# 16-key_Pro_Micro.net
KiCad netlist of a schematic drawn in EAGLE
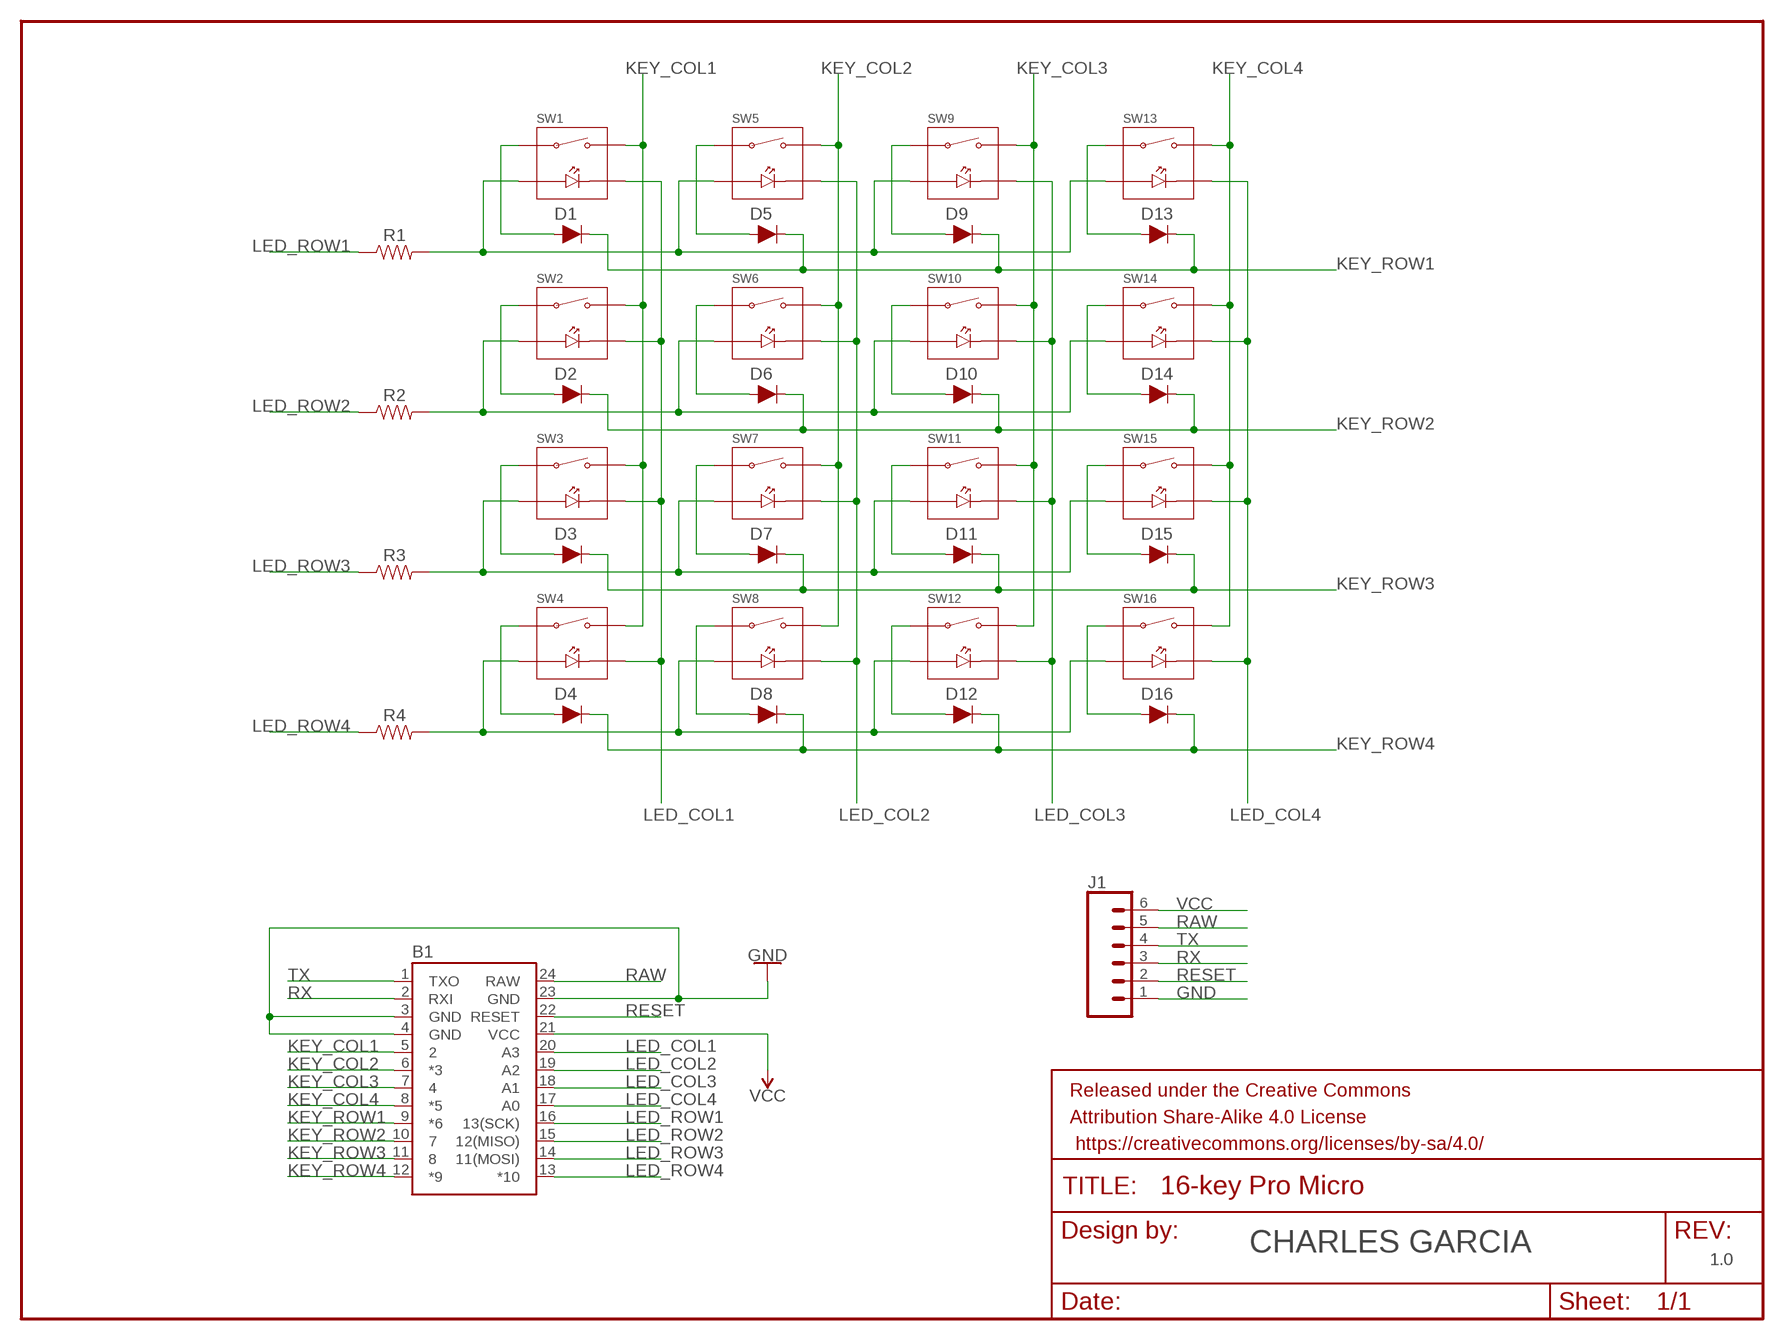
[diagram p0: schematic, sheet 1]

(export (version "E")
  (design (tool "Eeschema 10.0.6"))
  (components
    (comp (ref "B1")
      (value "SPARKFUN_PRO_MICRO")
      (footprint "eagle-import:SPARKFUN_PRO_MICRO")
      (libsource (lib "eagle-import") (part "SPARKFUN_PRO_MICRO"))
    )
    (comp (ref "D1")
      (value "DIODE-1N4148")
      (footprint "eagle-import:DIODE-1N4148")
      (libsource (lib "eagle-import") (part "DIODE-1N4148"))
    )
    (comp (ref "D2")
      (value "DIODE-1N4148")
      (footprint "eagle-import:DIODE-1N4148")
      (libsource (lib "eagle-import") (part "DIODE-1N4148"))
    )
    (comp (ref "D3")
      (value "DIODE-1N4148")
      (footprint "eagle-import:DIODE-1N4148")
      (libsource (lib "eagle-import") (part "DIODE-1N4148"))
    )
    (comp (ref "D4")
      (value "DIODE-1N4148")
      (footprint "eagle-import:DIODE-1N4148")
      (libsource (lib "eagle-import") (part "DIODE-1N4148"))
    )
    (comp (ref "D5")
      (value "DIODE-1N4148")
      (footprint "eagle-import:DIODE-1N4148")
      (libsource (lib "eagle-import") (part "DIODE-1N4148"))
    )
    (comp (ref "D6")
      (value "DIODE-1N4148")
      (footprint "eagle-import:DIODE-1N4148")
      (libsource (lib "eagle-import") (part "DIODE-1N4148"))
    )
    (comp (ref "D7")
      (value "DIODE-1N4148")
      (footprint "eagle-import:DIODE-1N4148")
      (libsource (lib "eagle-import") (part "DIODE-1N4148"))
    )
    (comp (ref "D8")
      (value "DIODE-1N4148")
      (footprint "eagle-import:DIODE-1N4148")
      (libsource (lib "eagle-import") (part "DIODE-1N4148"))
    )
    (comp (ref "D9")
      (value "DIODE-1N4148")
      (footprint "eagle-import:DIODE-1N4148")
      (libsource (lib "eagle-import") (part "DIODE-1N4148"))
    )
    (comp (ref "D10")
      (value "DIODE-1N4148")
      (footprint "eagle-import:DIODE-1N4148")
      (libsource (lib "eagle-import") (part "DIODE-1N4148"))
    )
    (comp (ref "D11")
      (value "DIODE-1N4148")
      (footprint "eagle-import:DIODE-1N4148")
      (libsource (lib "eagle-import") (part "DIODE-1N4148"))
    )
    (comp (ref "D12")
      (value "DIODE-1N4148")
      (footprint "eagle-import:DIODE-1N4148")
      (libsource (lib "eagle-import") (part "DIODE-1N4148"))
    )
    (comp (ref "D13")
      (value "DIODE-1N4148")
      (footprint "eagle-import:DIODE-1N4148")
      (libsource (lib "eagle-import") (part "DIODE-1N4148"))
    )
    (comp (ref "D14")
      (value "DIODE-1N4148")
      (footprint "eagle-import:DIODE-1N4148")
      (libsource (lib "eagle-import") (part "DIODE-1N4148"))
    )
    (comp (ref "D15")
      (value "DIODE-1N4148")
      (footprint "eagle-import:DIODE-1N4148")
      (libsource (lib "eagle-import") (part "DIODE-1N4148"))
    )
    (comp (ref "D16")
      (value "DIODE-1N4148")
      (footprint "eagle-import:DIODE-1N4148")
      (libsource (lib "eagle-import") (part "DIODE-1N4148"))
    )
    (comp (ref "FRAME1")
      (value "FRAME-LETTER")
      (footprint "eagle-import:CREATIVE_COMMONS")
      (fields (field (name "AUTHOR") "CHARLES GARCIA") (field (name "REV") "1.0"))
      (libsource (lib "eagle-import") (part "FRAME-LETTER"))
    )
    (comp (ref "J1")
      (value "CONN_06SILK_FEMALE_PTH")
      (footprint "eagle-import:1X06")
      (libsource (lib "eagle-import") (part "CONN_06SILK_FEMALE_PTH"))
    )
    (comp (ref "R1")
      (value "RESISTORAXIAL-0.3")
      (footprint "eagle-import:AXIAL-0.3")
      (libsource (lib "eagle-import") (part "RESISTORAXIAL-0.3"))
    )
    (comp (ref "R2")
      (value "RESISTORAXIAL-0.3")
      (footprint "eagle-import:AXIAL-0.3")
      (libsource (lib "eagle-import") (part "RESISTORAXIAL-0.3"))
    )
    (comp (ref "R3")
      (value "RESISTORAXIAL-0.3")
      (footprint "eagle-import:AXIAL-0.3")
      (libsource (lib "eagle-import") (part "RESISTORAXIAL-0.3"))
    )
    (comp (ref "R4")
      (value "RESISTORAXIAL-0.3")
      (footprint "eagle-import:AXIAL-0.3")
      (libsource (lib "eagle-import") (part "RESISTORAXIAL-0.3"))
    )
    (comp (ref "SW1")
      (value "CHERRY_MX_PCB_LED")
      (footprint "eagle-import:MX_PCB_MOUNT_LED")
      (libsource (lib "eagle-import") (part "CHERRY_MX_PCB_LED"))
    )
    (comp (ref "SW2")
      (value "CHERRY_MX_PCB_LED")
      (footprint "eagle-import:MX_PCB_MOUNT_LED")
      (libsource (lib "eagle-import") (part "CHERRY_MX_PCB_LED"))
    )
    (comp (ref "SW3")
      (value "CHERRY_MX_PCB_LED")
      (footprint "eagle-import:MX_PCB_MOUNT_LED")
      (libsource (lib "eagle-import") (part "CHERRY_MX_PCB_LED"))
    )
    (comp (ref "SW4")
      (value "CHERRY_MX_PCB_LED")
      (footprint "eagle-import:MX_PCB_MOUNT_LED")
      (libsource (lib "eagle-import") (part "CHERRY_MX_PCB_LED"))
    )
    (comp (ref "SW5")
      (value "CHERRY_MX_PCB_LED")
      (footprint "eagle-import:MX_PCB_MOUNT_LED")
      (libsource (lib "eagle-import") (part "CHERRY_MX_PCB_LED"))
    )
    (comp (ref "SW6")
      (value "CHERRY_MX_PCB_LED")
      (footprint "eagle-import:MX_PCB_MOUNT_LED")
      (libsource (lib "eagle-import") (part "CHERRY_MX_PCB_LED"))
    )
    (comp (ref "SW7")
      (value "CHERRY_MX_PCB_LED")
      (footprint "eagle-import:MX_PCB_MOUNT_LED")
      (libsource (lib "eagle-import") (part "CHERRY_MX_PCB_LED"))
    )
    (comp (ref "SW8")
      (value "CHERRY_MX_PCB_LED")
      (footprint "eagle-import:MX_PCB_MOUNT_LED")
      (libsource (lib "eagle-import") (part "CHERRY_MX_PCB_LED"))
    )
    (comp (ref "SW9")
      (value "CHERRY_MX_PCB_LED")
      (footprint "eagle-import:MX_PCB_MOUNT_LED")
      (libsource (lib "eagle-import") (part "CHERRY_MX_PCB_LED"))
    )
    (comp (ref "SW10")
      (value "CHERRY_MX_PCB_LED")
      (footprint "eagle-import:MX_PCB_MOUNT_LED")
      (libsource (lib "eagle-import") (part "CHERRY_MX_PCB_LED"))
    )
    (comp (ref "SW11")
      (value "CHERRY_MX_PCB_LED")
      (footprint "eagle-import:MX_PCB_MOUNT_LED")
      (libsource (lib "eagle-import") (part "CHERRY_MX_PCB_LED"))
    )
    (comp (ref "SW12")
      (value "CHERRY_MX_PCB_LED")
      (footprint "eagle-import:MX_PCB_MOUNT_LED")
      (libsource (lib "eagle-import") (part "CHERRY_MX_PCB_LED"))
    )
    (comp (ref "SW13")
      (value "CHERRY_MX_PCB_LED")
      (footprint "eagle-import:MX_PCB_MOUNT_LED")
      (libsource (lib "eagle-import") (part "CHERRY_MX_PCB_LED"))
    )
    (comp (ref "SW14")
      (value "CHERRY_MX_PCB_LED")
      (footprint "eagle-import:MX_PCB_MOUNT_LED")
      (libsource (lib "eagle-import") (part "CHERRY_MX_PCB_LED"))
    )
    (comp (ref "SW15")
      (value "CHERRY_MX_PCB_LED")
      (footprint "eagle-import:MX_PCB_MOUNT_LED")
      (libsource (lib "eagle-import") (part "CHERRY_MX_PCB_LED"))
    )
    (comp (ref "SW16")
      (value "CHERRY_MX_PCB_LED")
      (footprint "eagle-import:MX_PCB_MOUNT_LED")
      (libsource (lib "eagle-import") (part "CHERRY_MX_PCB_LED"))
    )
  )
  (nets
    (net (code "1") (name "/KEY_COL1") (class "Default")
      (node (ref "B1") (pin "5") (pinfunction "2_5") (pintype "bidirectional"))
      (node (ref "SW1") (pin "SW_OUT") (pinfunction "SW_OUT_SW_OUT") (pintype "bidirectional"))
      (node (ref "SW2") (pin "SW_OUT") (pinfunction "SW_OUT_SW_OUT") (pintype "bidirectional"))
      (node (ref "SW3") (pin "SW_OUT") (pinfunction "SW_OUT_SW_OUT") (pintype "bidirectional"))
      (node (ref "SW4") (pin "SW_OUT") (pinfunction "SW_OUT_SW_OUT") (pintype "bidirectional"))
    )
    (net (code "2") (name "/KEY_COL2") (class "Default")
      (node (ref "B1") (pin "6") (pinfunction "*3_6") (pintype "bidirectional"))
      (node (ref "SW5") (pin "SW_OUT") (pinfunction "SW_OUT_SW_OUT") (pintype "bidirectional"))
      (node (ref "SW6") (pin "SW_OUT") (pinfunction "SW_OUT_SW_OUT") (pintype "bidirectional"))
      (node (ref "SW7") (pin "SW_OUT") (pinfunction "SW_OUT_SW_OUT") (pintype "bidirectional"))
      (node (ref "SW8") (pin "SW_OUT") (pinfunction "SW_OUT_SW_OUT") (pintype "bidirectional"))
    )
    (net (code "3") (name "/KEY_COL3") (class "Default")
      (node (ref "B1") (pin "7") (pinfunction "4_7") (pintype "bidirectional"))
      (node (ref "SW10") (pin "SW_OUT") (pinfunction "SW_OUT_SW_OUT") (pintype "bidirectional"))
      (node (ref "SW11") (pin "SW_OUT") (pinfunction "SW_OUT_SW_OUT") (pintype "bidirectional"))
      (node (ref "SW12") (pin "SW_OUT") (pinfunction "SW_OUT_SW_OUT") (pintype "bidirectional"))
      (node (ref "SW9") (pin "SW_OUT") (pinfunction "SW_OUT_SW_OUT") (pintype "bidirectional"))
    )
    (net (code "4") (name "/KEY_COL4") (class "Default")
      (node (ref "B1") (pin "8") (pinfunction "*5_8") (pintype "bidirectional"))
      (node (ref "SW13") (pin "SW_OUT") (pinfunction "SW_OUT_SW_OUT") (pintype "bidirectional"))
      (node (ref "SW14") (pin "SW_OUT") (pinfunction "SW_OUT_SW_OUT") (pintype "bidirectional"))
      (node (ref "SW15") (pin "SW_OUT") (pinfunction "SW_OUT_SW_OUT") (pintype "bidirectional"))
      (node (ref "SW16") (pin "SW_OUT") (pinfunction "SW_OUT_SW_OUT") (pintype "bidirectional"))
    )
    (net (code "5") (name "/KEY_ROW1") (class "Default")
      (node (ref "B1") (pin "9") (pinfunction "*6_9") (pintype "bidirectional"))
      (node (ref "D1") (pin "C") (pinfunction "C_C") (pintype "passive"))
      (node (ref "D13") (pin "C") (pinfunction "C_C") (pintype "passive"))
      (node (ref "D5") (pin "C") (pinfunction "C_C") (pintype "passive"))
      (node (ref "D9") (pin "C") (pinfunction "C_C") (pintype "passive"))
    )
    (net (code "6") (name "/KEY_ROW2") (class "Default")
      (node (ref "B1") (pin "10") (pinfunction "7_10") (pintype "bidirectional"))
      (node (ref "D10") (pin "C") (pinfunction "C_C") (pintype "passive"))
      (node (ref "D14") (pin "C") (pinfunction "C_C") (pintype "passive"))
      (node (ref "D2") (pin "C") (pinfunction "C_C") (pintype "passive"))
      (node (ref "D6") (pin "C") (pinfunction "C_C") (pintype "passive"))
    )
    (net (code "7") (name "/KEY_ROW3") (class "Default")
      (node (ref "B1") (pin "11") (pinfunction "8_11") (pintype "bidirectional"))
      (node (ref "D11") (pin "C") (pinfunction "C_C") (pintype "passive"))
      (node (ref "D15") (pin "C") (pinfunction "C_C") (pintype "passive"))
      (node (ref "D3") (pin "C") (pinfunction "C_C") (pintype "passive"))
      (node (ref "D7") (pin "C") (pinfunction "C_C") (pintype "passive"))
    )
    (net (code "8") (name "/KEY_ROW4") (class "Default")
      (node (ref "B1") (pin "12") (pinfunction "*9_12") (pintype "bidirectional"))
      (node (ref "D12") (pin "C") (pinfunction "C_C") (pintype "passive"))
      (node (ref "D16") (pin "C") (pinfunction "C_C") (pintype "passive"))
      (node (ref "D4") (pin "C") (pinfunction "C_C") (pintype "passive"))
      (node (ref "D8") (pin "C") (pinfunction "C_C") (pintype "passive"))
    )
    (net (code "9") (name "/LED_COL1") (class "Default")
      (node (ref "B1") (pin "20") (pinfunction "A3_20") (pintype "bidirectional"))
      (node (ref "SW1") (pin "LED_OUT") (pinfunction "LED_OUT_LED_OUT") (pintype "bidirectional"))
      (node (ref "SW2") (pin "LED_OUT") (pinfunction "LED_OUT_LED_OUT") (pintype "bidirectional"))
      (node (ref "SW3") (pin "LED_OUT") (pinfunction "LED_OUT_LED_OUT") (pintype "bidirectional"))
      (node (ref "SW4") (pin "LED_OUT") (pinfunction "LED_OUT_LED_OUT") (pintype "bidirectional"))
    )
    (net (code "10") (name "/LED_COL2") (class "Default")
      (node (ref "B1") (pin "19") (pinfunction "A2_19") (pintype "bidirectional"))
      (node (ref "SW5") (pin "LED_OUT") (pinfunction "LED_OUT_LED_OUT") (pintype "bidirectional"))
      (node (ref "SW6") (pin "LED_OUT") (pinfunction "LED_OUT_LED_OUT") (pintype "bidirectional"))
      (node (ref "SW7") (pin "LED_OUT") (pinfunction "LED_OUT_LED_OUT") (pintype "bidirectional"))
      (node (ref "SW8") (pin "LED_OUT") (pinfunction "LED_OUT_LED_OUT") (pintype "bidirectional"))
    )
    (net (code "11") (name "/LED_COL3") (class "Default")
      (node (ref "B1") (pin "18") (pinfunction "A1_18") (pintype "bidirectional"))
      (node (ref "SW10") (pin "LED_OUT") (pinfunction "LED_OUT_LED_OUT") (pintype "bidirectional"))
      (node (ref "SW11") (pin "LED_OUT") (pinfunction "LED_OUT_LED_OUT") (pintype "bidirectional"))
      (node (ref "SW12") (pin "LED_OUT") (pinfunction "LED_OUT_LED_OUT") (pintype "bidirectional"))
      (node (ref "SW9") (pin "LED_OUT") (pinfunction "LED_OUT_LED_OUT") (pintype "bidirectional"))
    )
    (net (code "12") (name "/LED_COL4") (class "Default")
      (node (ref "B1") (pin "17") (pinfunction "A0_17") (pintype "bidirectional"))
      (node (ref "SW13") (pin "LED_OUT") (pinfunction "LED_OUT_LED_OUT") (pintype "bidirectional"))
      (node (ref "SW14") (pin "LED_OUT") (pinfunction "LED_OUT_LED_OUT") (pintype "bidirectional"))
      (node (ref "SW15") (pin "LED_OUT") (pinfunction "LED_OUT_LED_OUT") (pintype "bidirectional"))
      (node (ref "SW16") (pin "LED_OUT") (pinfunction "LED_OUT_LED_OUT") (pintype "bidirectional"))
    )
    (net (code "13") (name "/LED_ROW1") (class "Default")
      (node (ref "B1") (pin "16") (pinfunction "13(SCK)_16") (pintype "bidirectional"))
      (node (ref "R1") (pin "P$1") (pinfunction "1_P$1") (pintype "passive"))
    )
    (net (code "14") (name "/LED_ROW2") (class "Default")
      (node (ref "B1") (pin "15") (pinfunction "12(MISO)_15") (pintype "bidirectional"))
      (node (ref "R2") (pin "P$1") (pinfunction "1_P$1") (pintype "passive"))
    )
    (net (code "15") (name "/LED_ROW3") (class "Default")
      (node (ref "B1") (pin "14") (pinfunction "11(MOSI)_14") (pintype "bidirectional"))
      (node (ref "R3") (pin "P$1") (pinfunction "1_P$1") (pintype "passive"))
    )
    (net (code "16") (name "/LED_ROW4") (class "Default")
      (node (ref "B1") (pin "13") (pinfunction "*10_13") (pintype "bidirectional"))
      (node (ref "R4") (pin "P$1") (pinfunction "1_P$1") (pintype "passive"))
    )
    (net (code "17") (name "/RAW") (class "Default")
      (node (ref "B1") (pin "24") (pinfunction "RAW_24") (pintype "power_in"))
      (node (ref "J1") (pin "5") (pinfunction "5_5") (pintype "passive"))
    )
    (net (code "18") (name "/RESET") (class "Default")
      (node (ref "B1") (pin "22") (pinfunction "RESET_22") (pintype "bidirectional"))
      (node (ref "J1") (pin "2") (pinfunction "2_2") (pintype "passive"))
    )
    (net (code "19") (name "/RX") (class "Default")
      (node (ref "B1") (pin "2") (pinfunction "RXI_2") (pintype "bidirectional"))
      (node (ref "J1") (pin "3") (pinfunction "3_3") (pintype "passive"))
    )
    (net (code "20") (name "/TX") (class "Default")
      (node (ref "B1") (pin "1") (pinfunction "TXO_1") (pintype "bidirectional"))
      (node (ref "J1") (pin "4") (pinfunction "4_4") (pintype "passive"))
    )
    (net (code "21") (name "GND") (class "Default")
      (node (ref "B1") (pin "23") (pinfunction "GND_23") (pintype "power_in"))
      (node (ref "B1") (pin "3") (pinfunction "GND_3") (pintype "power_in"))
      (node (ref "B1") (pin "4") (pinfunction "GND_4") (pintype "power_in"))
      (node (ref "J1") (pin "1") (pinfunction "1_1") (pintype "passive"))
    )
    (net (code "22") (name "Net-(D1-PadA)") (class "Default")
      (node (ref "D1") (pin "A") (pinfunction "A_A") (pintype "passive"))
      (node (ref "SW1") (pin "SW_IN") (pinfunction "SW_IN_SW_IN") (pintype "bidirectional"))
    )
    (net (code "23") (name "Net-(D2-PadA)") (class "Default")
      (node (ref "D2") (pin "A") (pinfunction "A_A") (pintype "passive"))
      (node (ref "SW2") (pin "SW_IN") (pinfunction "SW_IN_SW_IN") (pintype "bidirectional"))
    )
    (net (code "24") (name "Net-(D3-PadA)") (class "Default")
      (node (ref "D3") (pin "A") (pinfunction "A_A") (pintype "passive"))
      (node (ref "SW3") (pin "SW_IN") (pinfunction "SW_IN_SW_IN") (pintype "bidirectional"))
    )
    (net (code "25") (name "Net-(D4-PadA)") (class "Default")
      (node (ref "D4") (pin "A") (pinfunction "A_A") (pintype "passive"))
      (node (ref "SW4") (pin "SW_IN") (pinfunction "SW_IN_SW_IN") (pintype "bidirectional"))
    )
    (net (code "26") (name "Net-(D5-PadA)") (class "Default")
      (node (ref "D5") (pin "A") (pinfunction "A_A") (pintype "passive"))
      (node (ref "SW5") (pin "SW_IN") (pinfunction "SW_IN_SW_IN") (pintype "bidirectional"))
    )
    (net (code "27") (name "Net-(D6-PadA)") (class "Default")
      (node (ref "D6") (pin "A") (pinfunction "A_A") (pintype "passive"))
      (node (ref "SW6") (pin "SW_IN") (pinfunction "SW_IN_SW_IN") (pintype "bidirectional"))
    )
    (net (code "28") (name "Net-(D7-PadA)") (class "Default")
      (node (ref "D7") (pin "A") (pinfunction "A_A") (pintype "passive"))
      (node (ref "SW7") (pin "SW_IN") (pinfunction "SW_IN_SW_IN") (pintype "bidirectional"))
    )
    (net (code "29") (name "Net-(D8-PadA)") (class "Default")
      (node (ref "D8") (pin "A") (pinfunction "A_A") (pintype "passive"))
      (node (ref "SW8") (pin "SW_IN") (pinfunction "SW_IN_SW_IN") (pintype "bidirectional"))
    )
    (net (code "30") (name "Net-(D9-PadA)") (class "Default")
      (node (ref "D9") (pin "A") (pinfunction "A_A") (pintype "passive"))
      (node (ref "SW9") (pin "SW_IN") (pinfunction "SW_IN_SW_IN") (pintype "bidirectional"))
    )
    (net (code "31") (name "Net-(D10-PadA)") (class "Default")
      (node (ref "D10") (pin "A") (pinfunction "A_A") (pintype "passive"))
      (node (ref "SW10") (pin "SW_IN") (pinfunction "SW_IN_SW_IN") (pintype "bidirectional"))
    )
    (net (code "32") (name "Net-(D11-PadA)") (class "Default")
      (node (ref "D11") (pin "A") (pinfunction "A_A") (pintype "passive"))
      (node (ref "SW11") (pin "SW_IN") (pinfunction "SW_IN_SW_IN") (pintype "bidirectional"))
    )
    (net (code "33") (name "Net-(D12-PadA)") (class "Default")
      (node (ref "D12") (pin "A") (pinfunction "A_A") (pintype "passive"))
      (node (ref "SW12") (pin "SW_IN") (pinfunction "SW_IN_SW_IN") (pintype "bidirectional"))
    )
    (net (code "34") (name "Net-(D13-PadA)") (class "Default")
      (node (ref "D13") (pin "A") (pinfunction "A_A") (pintype "passive"))
      (node (ref "SW13") (pin "SW_IN") (pinfunction "SW_IN_SW_IN") (pintype "bidirectional"))
    )
    (net (code "35") (name "Net-(D14-PadA)") (class "Default")
      (node (ref "D14") (pin "A") (pinfunction "A_A") (pintype "passive"))
      (node (ref "SW14") (pin "SW_IN") (pinfunction "SW_IN_SW_IN") (pintype "bidirectional"))
    )
    (net (code "36") (name "Net-(D15-PadA)") (class "Default")
      (node (ref "D15") (pin "A") (pinfunction "A_A") (pintype "passive"))
      (node (ref "SW15") (pin "SW_IN") (pinfunction "SW_IN_SW_IN") (pintype "bidirectional"))
    )
    (net (code "37") (name "Net-(D16-PadA)") (class "Default")
      (node (ref "D16") (pin "A") (pinfunction "A_A") (pintype "passive"))
      (node (ref "SW16") (pin "SW_IN") (pinfunction "SW_IN_SW_IN") (pintype "bidirectional"))
    )
    (net (code "38") (name "Net-(R1-2)") (class "Default")
      (node (ref "R1") (pin "P$2") (pinfunction "2_P$2") (pintype "passive"))
      (node (ref "SW1") (pin "LED_IN") (pinfunction "LED_IN_LED_IN") (pintype "bidirectional"))
      (node (ref "SW13") (pin "LED_IN") (pinfunction "LED_IN_LED_IN") (pintype "bidirectional"))
      (node (ref "SW5") (pin "LED_IN") (pinfunction "LED_IN_LED_IN") (pintype "bidirectional"))
      (node (ref "SW9") (pin "LED_IN") (pinfunction "LED_IN_LED_IN") (pintype "bidirectional"))
    )
    (net (code "39") (name "Net-(R2-2)") (class "Default")
      (node (ref "R2") (pin "P$2") (pinfunction "2_P$2") (pintype "passive"))
      (node (ref "SW10") (pin "LED_IN") (pinfunction "LED_IN_LED_IN") (pintype "bidirectional"))
      (node (ref "SW14") (pin "LED_IN") (pinfunction "LED_IN_LED_IN") (pintype "bidirectional"))
      (node (ref "SW2") (pin "LED_IN") (pinfunction "LED_IN_LED_IN") (pintype "bidirectional"))
      (node (ref "SW6") (pin "LED_IN") (pinfunction "LED_IN_LED_IN") (pintype "bidirectional"))
    )
    (net (code "40") (name "Net-(R3-2)") (class "Default")
      (node (ref "R3") (pin "P$2") (pinfunction "2_P$2") (pintype "passive"))
      (node (ref "SW11") (pin "LED_IN") (pinfunction "LED_IN_LED_IN") (pintype "bidirectional"))
      (node (ref "SW15") (pin "LED_IN") (pinfunction "LED_IN_LED_IN") (pintype "bidirectional"))
      (node (ref "SW3") (pin "LED_IN") (pinfunction "LED_IN_LED_IN") (pintype "bidirectional"))
      (node (ref "SW7") (pin "LED_IN") (pinfunction "LED_IN_LED_IN") (pintype "bidirectional"))
    )
    (net (code "41") (name "Net-(R4-2)") (class "Default")
      (node (ref "R4") (pin "P$2") (pinfunction "2_P$2") (pintype "passive"))
      (node (ref "SW12") (pin "LED_IN") (pinfunction "LED_IN_LED_IN") (pintype "bidirectional"))
      (node (ref "SW16") (pin "LED_IN") (pinfunction "LED_IN_LED_IN") (pintype "bidirectional"))
      (node (ref "SW4") (pin "LED_IN") (pinfunction "LED_IN_LED_IN") (pintype "bidirectional"))
      (node (ref "SW8") (pin "LED_IN") (pinfunction "LED_IN_LED_IN") (pintype "bidirectional"))
    )
    (net (code "42") (name "VCC") (class "Default")
      (node (ref "B1") (pin "21") (pinfunction "VCC_21") (pintype "power_in"))
      (node (ref "J1") (pin "6") (pinfunction "6_6") (pintype "passive"))
    )
  )
)
